# MCU.net
KiCad netlist of a schematic drawn in Altium Designer
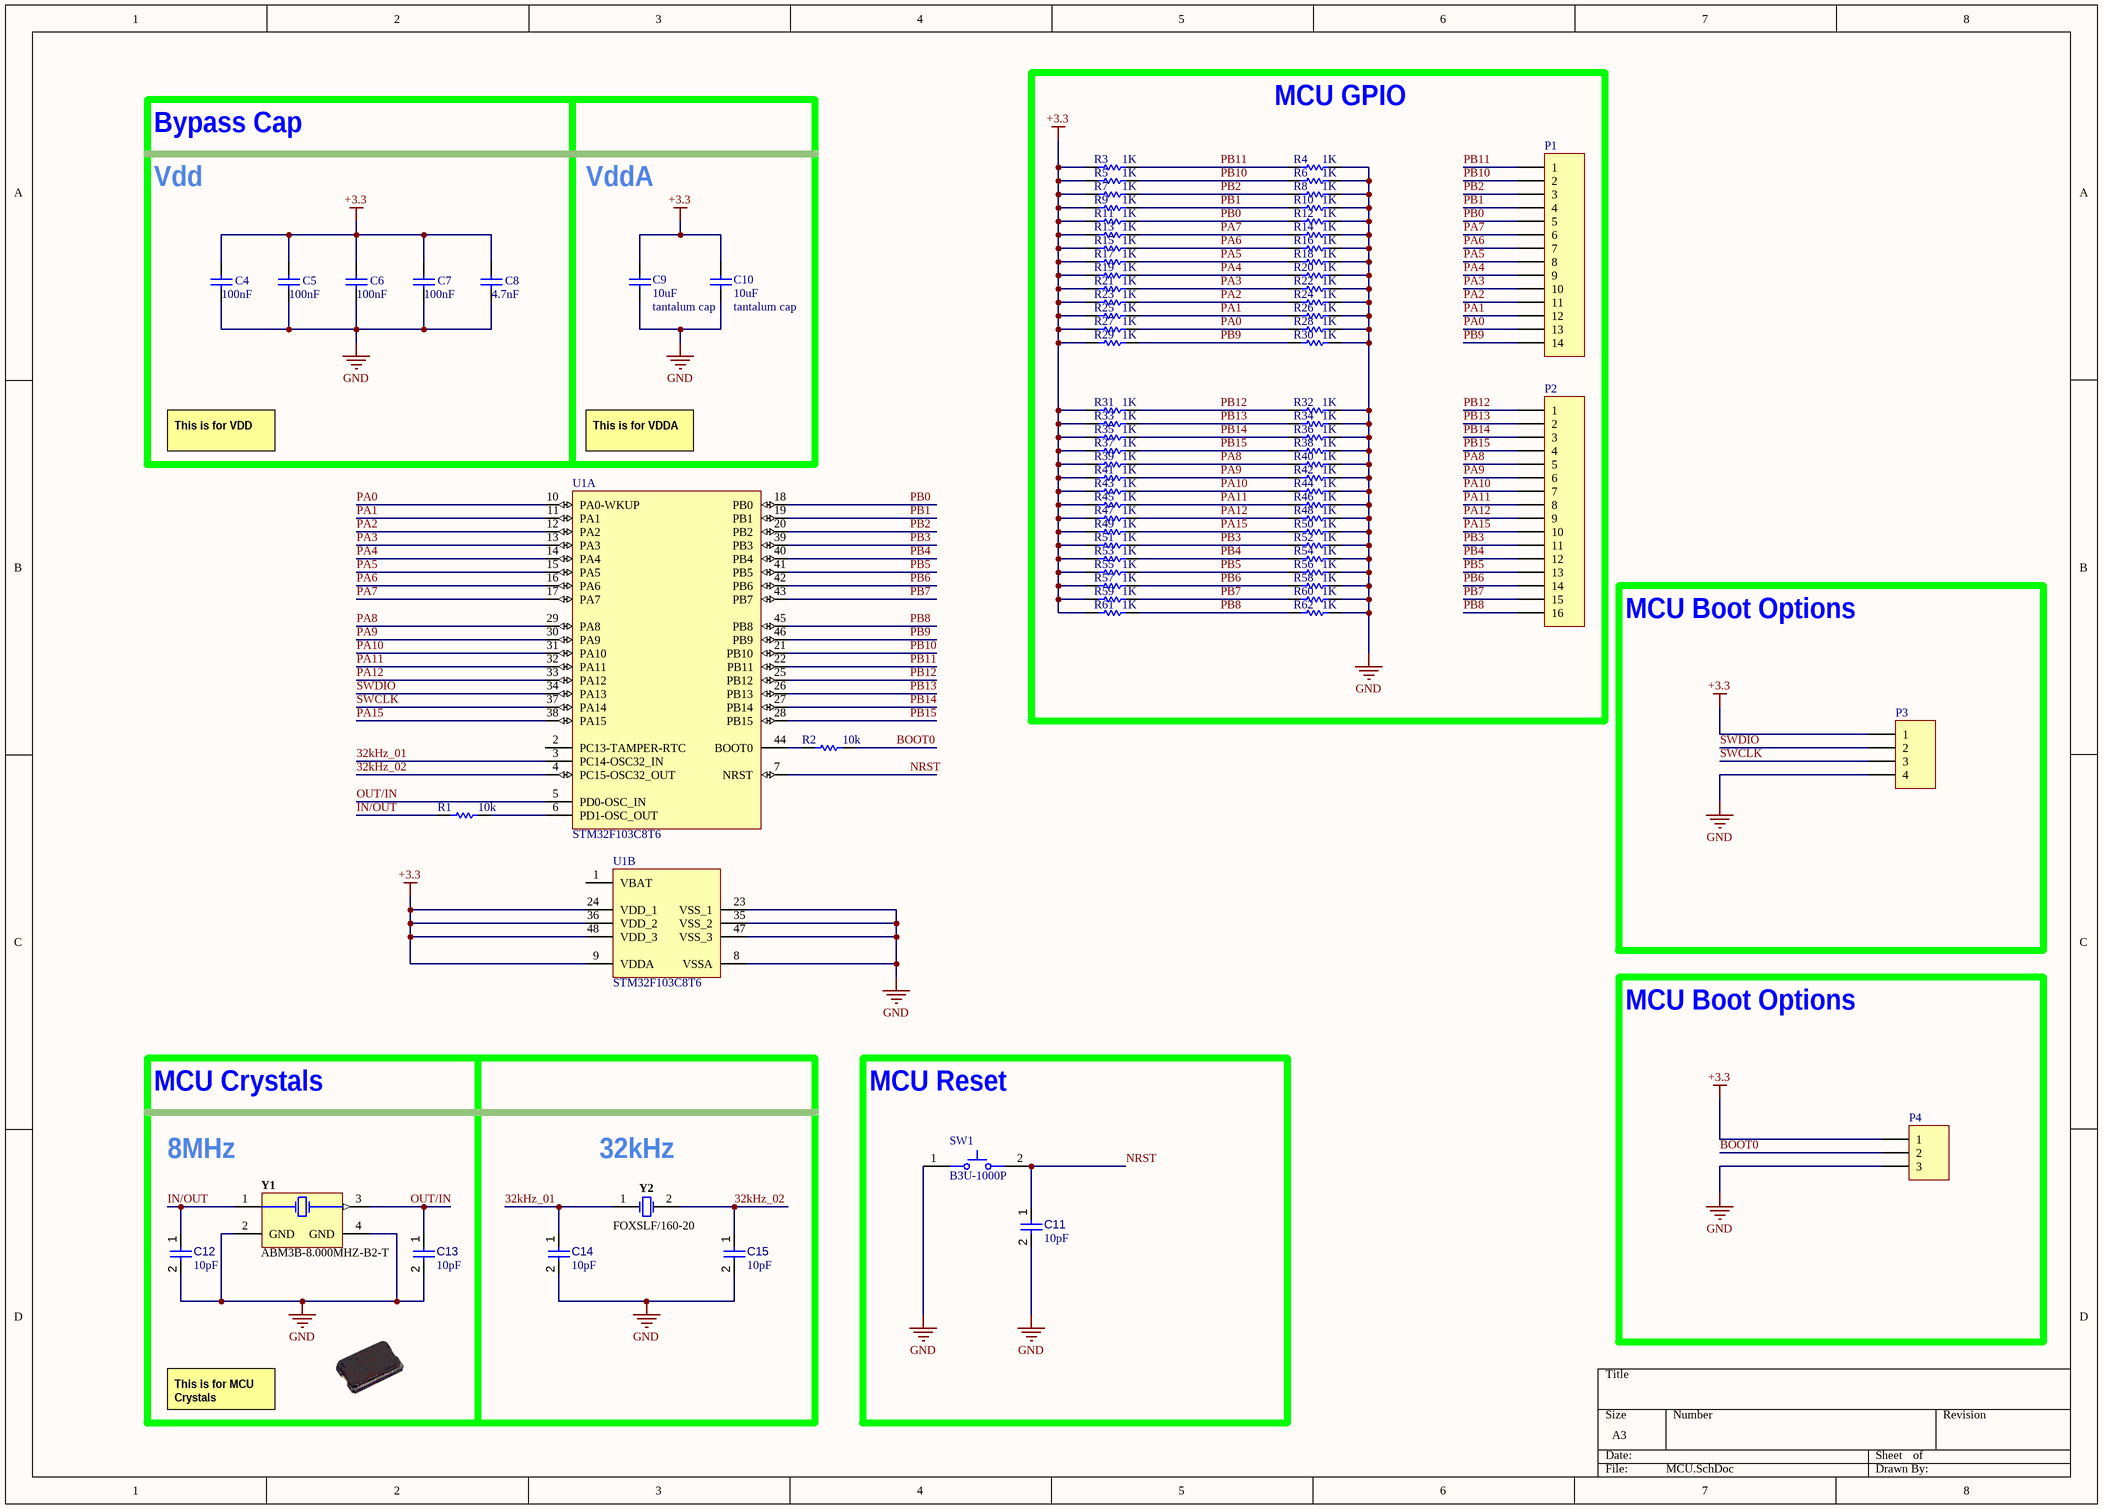
[diagram p0: MCU.SchDoc]

(export (version "E")
  (design (tool "Eeschema 10.0.6"))
  (components
    (comp (ref "C4")
      (value "100nF")
      (footprint "1608[0603]cap")
      (description "Capacitor (Semiconductor SIM Model)")
      (fields (field (name "Comment") "Cap Semi_1") (field (name "PUBLISHER") "Altium Limited"))
      (libsource (lib "smartmcu") (part "Cap Semi_1"))
    )
    (comp (ref "C5")
      (value "100nF")
      (footprint "CAPC2013X135X45NL10T25")
      (description "Capacitor (Semiconductor SIM Model)")
      (fields
        (field (name "Comment") "Capacitor 1 uF +/- 10% 50 V 0805")
        (field (name "PUBLISHER") "Altium Limited")
      )
      (libsource (lib "smartmcu") (part "Cap Semi_1"))
    )
    (comp (ref "C6")
      (value "100nF")
      (footprint "CAPC2013X135X45NL10T25")
      (description "Capacitor (Semiconductor SIM Model)")
      (fields
        (field (name "Comment") "Capacitor 1 uF +/- 10% 50 V 0805")
        (field (name "PUBLISHER") "Altium Limited")
      )
      (libsource (lib "smartmcu") (part "Cap Semi_1"))
    )
    (comp (ref "C7")
      (value "100nF")
      (footprint "CAPC2013X135X45NL10T25")
      (description "Capacitor (Semiconductor SIM Model)")
      (fields
        (field (name "Comment") "Capacitor 1 uF +/- 10% 50 V 0805")
        (field (name "PUBLISHER") "Altium Limited")
      )
      (libsource (lib "smartmcu") (part "Cap Semi_1"))
    )
    (comp (ref "C8")
      (value "4.7nF")
      (footprint "CAPC2013X135X45NL10T25")
      (description "Capacitor (Semiconductor SIM Model)")
      (fields
        (field (name "Comment") "Capacitor 1 uF +/- 10% 50 V 0805")
        (field (name "PUBLISHER") "Altium Limited")
      )
      (libsource (lib "smartmcu") (part "Cap Semi_1"))
    )
    (comp (ref "C9")
      (value "tantalum cap")
      (footprint "C1206tancap")
      (description "Capacitor (Semiconductor SIM Model)")
      (fields (field (name "ALTIUM_VALUE") "10uF") (field (name "PUBLISHER") "Altium Limited"))
      (libsource (lib "smartmcu") (part "Cap Semi_5"))
    )
    (comp (ref "C10")
      (value "tantalum cap")
      (footprint "C1206tancap")
      (description "Capacitor (Semiconductor SIM Model)")
      (fields (field (name "ALTIUM_VALUE") "10uF") (field (name "PUBLISHER") "Altium Limited"))
      (libsource (lib "smartmcu") (part "Cap Semi_5"))
    )
    (comp (ref "C11")
      (value "10pF")
      (footprint "CAPC1005X55X25ML05T05")
      (description "Chip Capacitor, 10 pF, +/- 5%, 50 V, 0402 (1005 Metric)")
      (fields (field (name "TOLERANCE") "5%") (field (name "Comment") "Capacitor 10 pF +/- 5% 50 V 0402"))
      (libsource (lib "Averna Test Systems") (part "CAP-NP-2"))
    )
    (comp (ref "C12")
      (value "10pF")
      (footprint "CAPC1005X55X25ML05T05")
      (description "Chip Capacitor, 10 pF, +/- 5%, 50 V, 0402 (1005 Metric)")
      (fields (field (name "TOLERANCE") "5%") (field (name "Comment") "Capacitor 10 pF +/- 5% 50 V 0402"))
      (libsource (lib "Averna Test Systems") (part "CAP-NP-2"))
    )
    (comp (ref "C13")
      (value "10pF")
      (footprint "CAPC1005X55X25ML05T05")
      (description "Chip Capacitor, 10 pF, +/- 5%, 50 V, 0402 (1005 Metric)")
      (fields (field (name "TOLERANCE") "5%") (field (name "Comment") "Capacitor 10 pF +/- 5% 50 V 0402"))
      (libsource (lib "Averna Test Systems") (part "CAP-NP-2"))
    )
    (comp (ref "C14")
      (value "10pF")
      (footprint "CAPC1005X55X25ML05T05")
      (description "Chip Capacitor, 10 pF, +/- 5%, 50 V, 0402 (1005 Metric)")
      (fields (field (name "TOLERANCE") "5%") (field (name "Comment") "Capacitor 10 pF +/- 5% 50 V 0402"))
      (libsource (lib "Averna Test Systems") (part "CAP-NP-2"))
    )
    (comp (ref "C15")
      (value "10pF")
      (footprint "CAPC1005X55X25ML05T05")
      (description "Chip Capacitor, 10 pF, +/- 5%, 50 V, 0402 (1005 Metric)")
      (fields (field (name "TOLERANCE") "5%") (field (name "Comment") "Capacitor 10 pF +/- 5% 50 V 0402"))
      (libsource (lib "Averna Test Systems") (part "CAP-NP-2"))
    )
    (comp (ref "P1")
      (value "Header 14")
      (footprint "My_1X14")
      (description "Header, 14-Pin")
      (fields (field (name "ASID PART NUMBER") "Header 14-AS"))
      (libsource (lib "Mylib_Rev_4") (part "Header 14"))
    )
    (comp (ref "P2")
      (value "Header 16")
      (footprint "MY_FE16")
      (description "Header, 16-Pin")
      (fields (field (name "ASID PART NUMBER") "Header 16-AS"))
      (libsource (lib "Mylib_Rev_4") (part "Header 16"))
    )
    (comp (ref "P3")
      (value "Header 4")
      (footprint "My_1X04")
      (description "Header, 4-Pin")
      (fields (field (name "ASID PART NUMBER") "Header 4-AS"))
      (libsource (lib "Mylib_Rev_4") (part "Header 4"))
    )
    (comp (ref "P4")
      (value "Header 3")
      (footprint "My_1X03")
      (description "Header, 3-Pin")
      (fields (field (name "ASID PART NUMBER") "Header 3-AS"))
      (libsource (lib "Mylib_Rev_4") (part "Header 3"))
    )
    (comp (ref "R1")
      (value "10k")
      (footprint "MY_0603")
      (description "Standard resistor")
      (fields (field (name "ASID PART NUMBER") "Res-AS"))
      (libsource (lib "Mylib_Rev_4") (part "Res"))
    )
    (comp (ref "R2")
      (value "10k")
      (footprint "MY_0603")
      (description "Standard resistor")
      (fields (field (name "ASID PART NUMBER") "Res-AS"))
      (libsource (lib "Mylib_Rev_4") (part "Res"))
    )
    (comp (ref "R3")
      (value "1K")
      (footprint "MY_0603")
      (description "Standard resistor")
      (fields (field (name "ASID PART NUMBER") "Res-AS"))
      (libsource (lib "Mylib_Rev_4") (part "Res"))
    )
    (comp (ref "R4")
      (value "1K")
      (footprint "MY_0603")
      (description "Standard resistor")
      (fields (field (name "ASID PART NUMBER") "Res-AS"))
      (libsource (lib "Mylib_Rev_4") (part "Res"))
    )
    (comp (ref "R5")
      (value "1K")
      (footprint "MY_0603")
      (description "Standard resistor")
      (fields (field (name "ASID PART NUMBER") "Res-AS"))
      (libsource (lib "Mylib_Rev_4") (part "Res"))
    )
    (comp (ref "R6")
      (value "1K")
      (footprint "MY_0603")
      (description "Standard resistor")
      (fields (field (name "ASID PART NUMBER") "Res-AS"))
      (libsource (lib "Mylib_Rev_4") (part "Res"))
    )
    (comp (ref "R7")
      (value "1K")
      (footprint "MY_0603")
      (description "Standard resistor")
      (fields (field (name "ASID PART NUMBER") "Res-AS"))
      (libsource (lib "Mylib_Rev_4") (part "Res"))
    )
    (comp (ref "R8")
      (value "1K")
      (footprint "MY_0603")
      (description "Standard resistor")
      (fields (field (name "ASID PART NUMBER") "Res-AS"))
      (libsource (lib "Mylib_Rev_4") (part "Res"))
    )
    (comp (ref "R9")
      (value "1K")
      (footprint "MY_0603")
      (description "Standard resistor")
      (fields (field (name "ASID PART NUMBER") "Res-AS"))
      (libsource (lib "Mylib_Rev_4") (part "Res"))
    )
    (comp (ref "R10")
      (value "1K")
      (footprint "MY_0603")
      (description "Standard resistor")
      (fields (field (name "ASID PART NUMBER") "Res-AS"))
      (libsource (lib "Mylib_Rev_4") (part "Res"))
    )
    (comp (ref "R11")
      (value "1K")
      (footprint "MY_0603")
      (description "Standard resistor")
      (fields (field (name "ASID PART NUMBER") "Res-AS"))
      (libsource (lib "Mylib_Rev_4") (part "Res"))
    )
    (comp (ref "R12")
      (value "1K")
      (footprint "MY_0603")
      (description "Standard resistor")
      (fields (field (name "ASID PART NUMBER") "Res-AS"))
      (libsource (lib "Mylib_Rev_4") (part "Res"))
    )
    (comp (ref "R13")
      (value "1K")
      (footprint "MY_0603")
      (description "Standard resistor")
      (fields (field (name "ASID PART NUMBER") "Res-AS"))
      (libsource (lib "Mylib_Rev_4") (part "Res"))
    )
    (comp (ref "R14")
      (value "1K")
      (footprint "MY_0603")
      (description "Standard resistor")
      (fields (field (name "ASID PART NUMBER") "Res-AS"))
      (libsource (lib "Mylib_Rev_4") (part "Res"))
    )
    (comp (ref "R15")
      (value "1K")
      (footprint "MY_0603")
      (description "Standard resistor")
      (fields (field (name "ASID PART NUMBER") "Res-AS"))
      (libsource (lib "Mylib_Rev_4") (part "Res"))
    )
    (comp (ref "R16")
      (value "1K")
      (footprint "MY_0603")
      (description "Standard resistor")
      (fields (field (name "ASID PART NUMBER") "Res-AS"))
      (libsource (lib "Mylib_Rev_4") (part "Res"))
    )
    (comp (ref "R17")
      (value "1K")
      (footprint "MY_0603")
      (description "Standard resistor")
      (fields (field (name "ASID PART NUMBER") "Res-AS"))
      (libsource (lib "Mylib_Rev_4") (part "Res"))
    )
    (comp (ref "R18")
      (value "1K")
      (footprint "MY_0603")
      (description "Standard resistor")
      (fields (field (name "ASID PART NUMBER") "Res-AS"))
      (libsource (lib "Mylib_Rev_4") (part "Res"))
    )
    (comp (ref "R19")
      (value "1K")
      (footprint "MY_0603")
      (description "Standard resistor")
      (fields (field (name "ASID PART NUMBER") "Res-AS"))
      (libsource (lib "Mylib_Rev_4") (part "Res"))
    )
    (comp (ref "R20")
      (value "1K")
      (footprint "MY_0603")
      (description "Standard resistor")
      (fields (field (name "ASID PART NUMBER") "Res-AS"))
      (libsource (lib "Mylib_Rev_4") (part "Res"))
    )
    (comp (ref "R21")
      (value "1K")
      (footprint "MY_0603")
      (description "Standard resistor")
      (fields (field (name "ASID PART NUMBER") "Res-AS"))
      (libsource (lib "Mylib_Rev_4") (part "Res"))
    )
    (comp (ref "R22")
      (value "1K")
      (footprint "MY_0603")
      (description "Standard resistor")
      (fields (field (name "ASID PART NUMBER") "Res-AS"))
      (libsource (lib "Mylib_Rev_4") (part "Res"))
    )
    (comp (ref "R23")
      (value "1K")
      (footprint "MY_0603")
      (description "Standard resistor")
      (fields (field (name "ASID PART NUMBER") "Res-AS"))
      (libsource (lib "Mylib_Rev_4") (part "Res"))
    )
    (comp (ref "R24")
      (value "1K")
      (footprint "MY_0603")
      (description "Standard resistor")
      (fields (field (name "ASID PART NUMBER") "Res-AS"))
      (libsource (lib "Mylib_Rev_4") (part "Res"))
    )
    (comp (ref "R25")
      (value "1K")
      (footprint "MY_0603")
      (description "Standard resistor")
      (fields (field (name "ASID PART NUMBER") "Res-AS"))
      (libsource (lib "Mylib_Rev_4") (part "Res"))
    )
    (comp (ref "R26")
      (value "1K")
      (footprint "MY_0603")
      (description "Standard resistor")
      (fields (field (name "ASID PART NUMBER") "Res-AS"))
      (libsource (lib "Mylib_Rev_4") (part "Res"))
    )
    (comp (ref "R27")
      (value "1K")
      (footprint "MY_0603")
      (description "Standard resistor")
      (fields (field (name "ASID PART NUMBER") "Res-AS"))
      (libsource (lib "Mylib_Rev_4") (part "Res"))
    )
    (comp (ref "R28")
      (value "1K")
      (footprint "MY_0603")
      (description "Standard resistor")
      (fields (field (name "ASID PART NUMBER") "Res-AS"))
      (libsource (lib "Mylib_Rev_4") (part "Res"))
    )
    (comp (ref "R29")
      (value "1K")
      (footprint "MY_0603")
      (description "Standard resistor")
      (fields (field (name "ASID PART NUMBER") "Res-AS"))
      (libsource (lib "Mylib_Rev_4") (part "Res"))
    )
    (comp (ref "R30")
      (value "1K")
      (footprint "MY_0603")
      (description "Standard resistor")
      (fields (field (name "ASID PART NUMBER") "Res-AS"))
      (libsource (lib "Mylib_Rev_4") (part "Res"))
    )
    (comp (ref "R31")
      (value "1K")
      (footprint "MY_0603")
      (description "Standard resistor")
      (fields (field (name "ASID PART NUMBER") "Res-AS"))
      (libsource (lib "Mylib_Rev_4") (part "Res"))
    )
    (comp (ref "R32")
      (value "1K")
      (footprint "MY_0603")
      (description "Standard resistor")
      (fields (field (name "ASID PART NUMBER") "Res-AS"))
      (libsource (lib "Mylib_Rev_4") (part "Res"))
    )
    (comp (ref "R33")
      (value "1K")
      (footprint "MY_0603")
      (description "Standard resistor")
      (fields (field (name "ASID PART NUMBER") "Res-AS"))
      (libsource (lib "Mylib_Rev_4") (part "Res"))
    )
    (comp (ref "R34")
      (value "1K")
      (footprint "MY_0603")
      (description "Standard resistor")
      (fields (field (name "ASID PART NUMBER") "Res-AS"))
      (libsource (lib "Mylib_Rev_4") (part "Res"))
    )
    (comp (ref "R35")
      (value "1K")
      (footprint "MY_0603")
      (description "Standard resistor")
      (fields (field (name "ASID PART NUMBER") "Res-AS"))
      (libsource (lib "Mylib_Rev_4") (part "Res"))
    )
    (comp (ref "R36")
      (value "1K")
      (footprint "MY_0603")
      (description "Standard resistor")
      (fields (field (name "ASID PART NUMBER") "Res-AS"))
      (libsource (lib "Mylib_Rev_4") (part "Res"))
    )
    (comp (ref "R37")
      (value "1K")
      (footprint "MY_0603")
      (description "Standard resistor")
      (fields (field (name "ASID PART NUMBER") "Res-AS"))
      (libsource (lib "Mylib_Rev_4") (part "Res"))
    )
    (comp (ref "R38")
      (value "1K")
      (footprint "MY_0603")
      (description "Standard resistor")
      (fields (field (name "ASID PART NUMBER") "Res-AS"))
      (libsource (lib "Mylib_Rev_4") (part "Res"))
    )
    (comp (ref "R39")
      (value "1K")
      (footprint "MY_0603")
      (description "Standard resistor")
      (fields (field (name "ASID PART NUMBER") "Res-AS"))
      (libsource (lib "Mylib_Rev_4") (part "Res"))
    )
    (comp (ref "R40")
      (value "1K")
      (footprint "MY_0603")
      (description "Standard resistor")
      (fields (field (name "ASID PART NUMBER") "Res-AS"))
      (libsource (lib "Mylib_Rev_4") (part "Res"))
    )
    (comp (ref "R41")
      (value "1K")
      (footprint "MY_0603")
      (description "Standard resistor")
      (fields (field (name "ASID PART NUMBER") "Res-AS"))
      (libsource (lib "Mylib_Rev_4") (part "Res"))
    )
    (comp (ref "R42")
      (value "1K")
      (footprint "MY_0603")
      (description "Standard resistor")
      (fields (field (name "ASID PART NUMBER") "Res-AS"))
      (libsource (lib "Mylib_Rev_4") (part "Res"))
    )
    (comp (ref "R43")
      (value "1K")
      (footprint "MY_0603")
      (description "Standard resistor")
      (fields (field (name "ASID PART NUMBER") "Res-AS"))
      (libsource (lib "Mylib_Rev_4") (part "Res"))
    )
    (comp (ref "R44")
      (value "1K")
      (footprint "MY_0603")
      (description "Standard resistor")
      (fields (field (name "ASID PART NUMBER") "Res-AS"))
      (libsource (lib "Mylib_Rev_4") (part "Res"))
    )
    (comp (ref "R45")
      (value "1K")
      (footprint "MY_0603")
      (description "Standard resistor")
      (fields (field (name "ASID PART NUMBER") "Res-AS"))
      (libsource (lib "Mylib_Rev_4") (part "Res"))
    )
    (comp (ref "R46")
      (value "1K")
      (footprint "MY_0603")
      (description "Standard resistor")
      (fields (field (name "ASID PART NUMBER") "Res-AS"))
      (libsource (lib "Mylib_Rev_4") (part "Res"))
    )
    (comp (ref "R47")
      (value "1K")
      (footprint "MY_0603")
      (description "Standard resistor")
      (fields (field (name "ASID PART NUMBER") "Res-AS"))
      (libsource (lib "Mylib_Rev_4") (part "Res"))
    )
    (comp (ref "R48")
      (value "1K")
      (footprint "MY_0603")
      (description "Standard resistor")
      (fields (field (name "ASID PART NUMBER") "Res-AS"))
      (libsource (lib "Mylib_Rev_4") (part "Res"))
    )
    (comp (ref "R49")
      (value "1K")
      (footprint "MY_0603")
      (description "Standard resistor")
      (fields (field (name "ASID PART NUMBER") "Res-AS"))
      (libsource (lib "Mylib_Rev_4") (part "Res"))
    )
    (comp (ref "R50")
      (value "1K")
      (footprint "MY_0603")
      (description "Standard resistor")
      (fields (field (name "ASID PART NUMBER") "Res-AS"))
      (libsource (lib "Mylib_Rev_4") (part "Res"))
    )
    (comp (ref "R51")
      (value "1K")
      (footprint "MY_0603")
      (description "Standard resistor")
      (fields (field (name "ASID PART NUMBER") "Res-AS"))
      (libsource (lib "Mylib_Rev_4") (part "Res"))
    )
    (comp (ref "R52")
      (value "1K")
      (footprint "MY_0603")
      (description "Standard resistor")
      (fields (field (name "ASID PART NUMBER") "Res-AS"))
      (libsource (lib "Mylib_Rev_4") (part "Res"))
    )
    (comp (ref "R53")
      (value "1K")
      (footprint "MY_0603")
      (description "Standard resistor")
      (fields (field (name "ASID PART NUMBER") "Res-AS"))
      (libsource (lib "Mylib_Rev_4") (part "Res"))
    )
    (comp (ref "R54")
      (value "1K")
      (footprint "MY_0603")
      (description "Standard resistor")
      (fields (field (name "ASID PART NUMBER") "Res-AS"))
      (libsource (lib "Mylib_Rev_4") (part "Res"))
    )
    (comp (ref "R55")
      (value "1K")
      (footprint "MY_0603")
      (description "Standard resistor")
      (fields (field (name "ASID PART NUMBER") "Res-AS"))
      (libsource (lib "Mylib_Rev_4") (part "Res"))
    )
    (comp (ref "R56")
      (value "1K")
      (footprint "MY_0603")
      (description "Standard resistor")
      (fields (field (name "ASID PART NUMBER") "Res-AS"))
      (libsource (lib "Mylib_Rev_4") (part "Res"))
    )
    (comp (ref "R57")
      (value "1K")
      (footprint "MY_0603")
      (description "Standard resistor")
      (fields (field (name "ASID PART NUMBER") "Res-AS"))
      (libsource (lib "Mylib_Rev_4") (part "Res"))
    )
    (comp (ref "R58")
      (value "1K")
      (footprint "MY_0603")
      (description "Standard resistor")
      (fields (field (name "ASID PART NUMBER") "Res-AS"))
      (libsource (lib "Mylib_Rev_4") (part "Res"))
    )
    (comp (ref "R59")
      (value "1K")
      (footprint "MY_0603")
      (description "Standard resistor")
      (fields (field (name "ASID PART NUMBER") "Res-AS"))
      (libsource (lib "Mylib_Rev_4") (part "Res"))
    )
    (comp (ref "R60")
      (value "1K")
      (footprint "MY_0603")
      (description "Standard resistor")
      (fields (field (name "ASID PART NUMBER") "Res-AS"))
      (libsource (lib "Mylib_Rev_4") (part "Res"))
    )
    (comp (ref "R61")
      (value "1K")
      (footprint "MY_0603")
      (description "Standard resistor")
      (fields (field (name "ASID PART NUMBER") "Res-AS"))
      (libsource (lib "Mylib_Rev_4") (part "Res"))
    )
    (comp (ref "R62")
      (value "1K")
      (footprint "MY_0603")
      (description "Standard resistor")
      (fields (field (name "ASID PART NUMBER") "Res-AS"))
      (libsource (lib "Mylib_Rev_4") (part "Res"))
    )
    (comp (ref "SW1")
      (value "B3U-1000P")
      (footprint "OMRON-B3U-1000_V")
      (description "Tactile Switch, SPST-NO, 0.05 A, 12 V, -25 to 70 degC, 2-Pin SMD, RoHS, Tape and Reel")
      (fields (field (name "MANUFACTURER") "Omron Electronic Components"))
      (libsource (lib "Averna Test Systems") (part "SW-SPST-NO-2"))
    )
    (comp (ref "U1")
      (value "STM32F103C8T6")
      (footprint "STM-LQFP48_L")
      (libsource (lib "Altium Content Vault") (part "MC-ARM-STM32F103X8_B-SQ48"))
    )
    (comp (ref "Y1")
      (value "ABM3B-8.000MHZ-B2-T")
      (footprint "ABRA-ABM3B_V")
      (description "Ceramic SMD Crystal, 8 MHz, +/- 20 ppm, 18 pF, -20 to 70 degC, 4-Pin SMD, RoHS, Tape and Reel")
      (fields (field (name "TOLERANCE") "20ppm") (field (name "MANUFACTURER") "Abracon"))
      (libsource (lib "Averna Test Systems") (part "XTAL-1-3-4"))
    )
    (comp (ref "Y2")
      (value "FOXSLF/160-20")
      (footprint "FOX-FOXSLF160-20")
      (fields (field (name "MANUFACTURER") "FOX Electronics") (field (name "TOLERANCE") "50ppm"))
      (libsource (lib "Averna Test Systems") (part "XTAL-1-2-2"))
    )
  )
  (nets
    (net (code "1") (name "+3.3") (class "Default")
      (node (ref "C10") (pin "2") (pinfunction "2_2") (pintype "passive"))
      (node (ref "C4") (pin "2") (pinfunction "2_2") (pintype "passive"))
      (node (ref "C5") (pin "2") (pinfunction "2_2") (pintype "passive"))
      (node (ref "C6") (pin "2") (pinfunction "2_2") (pintype "passive"))
      (node (ref "C7") (pin "2") (pinfunction "2_2") (pintype "passive"))
      (node (ref "C8") (pin "2") (pinfunction "2_2") (pintype "passive"))
      (node (ref "C9") (pin "2") (pinfunction "2_2") (pintype "passive"))
      (node (ref "P3") (pin "1") (pinfunction "1_1") (pintype "passive"))
      (node (ref "P4") (pin "1") (pinfunction "1_1") (pintype "passive"))
      (node (ref "R11") (pin "1") (pinfunction "1_1") (pintype "passive"))
      (node (ref "R13") (pin "1") (pinfunction "1_1") (pintype "passive"))
      (node (ref "R15") (pin "1") (pinfunction "1_1") (pintype "passive"))
      (node (ref "R17") (pin "1") (pinfunction "1_1") (pintype "passive"))
      (node (ref "R19") (pin "1") (pinfunction "1_1") (pintype "passive"))
      (node (ref "R21") (pin "1") (pinfunction "1_1") (pintype "passive"))
      (node (ref "R23") (pin "1") (pinfunction "1_1") (pintype "passive"))
      (node (ref "R25") (pin "1") (pinfunction "1_1") (pintype "passive"))
      (node (ref "R27") (pin "1") (pinfunction "1_1") (pintype "passive"))
      (node (ref "R29") (pin "1") (pinfunction "1_1") (pintype "passive"))
      (node (ref "R3") (pin "1") (pinfunction "1_1") (pintype "passive"))
      (node (ref "R31") (pin "1") (pinfunction "1_1") (pintype "passive"))
      (node (ref "R33") (pin "1") (pinfunction "1_1") (pintype "passive"))
      (node (ref "R35") (pin "1") (pinfunction "1_1") (pintype "passive"))
      (node (ref "R37") (pin "1") (pinfunction "1_1") (pintype "passive"))
      (node (ref "R39") (pin "1") (pinfunction "1_1") (pintype "passive"))
      (node (ref "R41") (pin "1") (pinfunction "1_1") (pintype "passive"))
      (node (ref "R43") (pin "1") (pinfunction "1_1") (pintype "passive"))
      (node (ref "R45") (pin "1") (pinfunction "1_1") (pintype "passive"))
      (node (ref "R47") (pin "1") (pinfunction "1_1") (pintype "passive"))
      (node (ref "R49") (pin "1") (pinfunction "1_1") (pintype "passive"))
      (node (ref "R5") (pin "1") (pinfunction "1_1") (pintype "passive"))
      (node (ref "R51") (pin "1") (pinfunction "1_1") (pintype "passive"))
      (node (ref "R53") (pin "1") (pinfunction "1_1") (pintype "passive"))
      (node (ref "R55") (pin "1") (pinfunction "1_1") (pintype "passive"))
      (node (ref "R57") (pin "1") (pinfunction "1_1") (pintype "passive"))
      (node (ref "R59") (pin "1") (pinfunction "1_1") (pintype "passive"))
      (node (ref "R61") (pin "1") (pinfunction "1_1") (pintype "passive"))
      (node (ref "R7") (pin "1") (pinfunction "1_1") (pintype "passive"))
      (node (ref "R9") (pin "1") (pinfunction "1_1") (pintype "passive"))
      (node (ref "U1") (pin "24") (pinfunction "VDD_1_24") (pintype "power_in"))
      (node (ref "U1") (pin "36") (pinfunction "VDD_2_36") (pintype "power_in"))
      (node (ref "U1") (pin "48") (pinfunction "VDD_3_48") (pintype "power_in"))
      (node (ref "U1") (pin "9") (pinfunction "VDDA_9") (pintype "power_in"))
    )
    (net (code "2") (name "/32kHz_01") (class "Default")
      (node (ref "C14") (pin "1") (pinfunction "1_1") (pintype "passive"))
      (node (ref "U1") (pin "3") (pinfunction "PC14-OSC32_IN_3") (pintype "passive"))
      (node (ref "Y2") (pin "1") (pinfunction "1_1") (pintype "passive"))
    )
    (net (code "3") (name "/32kHz_02") (class "Default")
      (node (ref "C15") (pin "1") (pinfunction "1_1") (pintype "passive"))
      (node (ref "U1") (pin "4") (pinfunction "PC15-OSC32_OUT_4") (pintype "bidirectional"))
      (node (ref "Y2") (pin "2") (pinfunction "2_2") (pintype "passive"))
    )
    (net (code "4") (name "/BOOT0") (class "Default")
      (node (ref "P4") (pin "2") (pinfunction "2_2") (pintype "passive"))
      (node (ref "R2") (pin "2") (pinfunction "2_2") (pintype "passive"))
    )
    (net (code "5") (name "/IN{slash}OUT") (class "Default")
      (node (ref "C12") (pin "1") (pinfunction "1_1") (pintype "passive"))
      (node (ref "R1") (pin "1") (pinfunction "1_1") (pintype "passive"))
      (node (ref "Y1") (pin "1") (pinfunction "X1_1") (pintype "passive"))
    )
    (net (code "6") (name "/NRST") (class "Default")
      (node (ref "C11") (pin "1") (pinfunction "1_1") (pintype "passive"))
      (node (ref "SW1") (pin "2") (pinfunction "2_2") (pintype "passive"))
      (node (ref "U1") (pin "7") (pinfunction "NRST_7") (pintype "bidirectional"))
    )
    (net (code "7") (name "/OUT{slash}IN") (class "Default")
      (node (ref "C13") (pin "1") (pinfunction "1_1") (pintype "passive"))
      (node (ref "U1") (pin "5") (pinfunction "PD0-OSC_IN_5") (pintype "passive"))
      (node (ref "Y1") (pin "3") (pinfunction "X2_3") (pintype "output"))
    )
    (net (code "8") (name "/PA0") (class "Default")
      (node (ref "P1") (pin "13") (pinfunction "13_13") (pintype "passive"))
      (node (ref "R27") (pin "2") (pinfunction "2_2") (pintype "passive"))
      (node (ref "R28") (pin "1") (pinfunction "1_1") (pintype "passive"))
      (node (ref "U1") (pin "10") (pinfunction "PA0-WKUP_10") (pintype "bidirectional"))
    )
    (net (code "9") (name "/PA1") (class "Default")
      (node (ref "P1") (pin "12") (pinfunction "12_12") (pintype "passive"))
      (node (ref "R25") (pin "2") (pinfunction "2_2") (pintype "passive"))
      (node (ref "R26") (pin "1") (pinfunction "1_1") (pintype "passive"))
      (node (ref "U1") (pin "11") (pinfunction "PA1_11") (pintype "bidirectional"))
    )
    (net (code "10") (name "/PA2") (class "Default")
      (node (ref "P1") (pin "11") (pinfunction "11_11") (pintype "passive"))
      (node (ref "R23") (pin "2") (pinfunction "2_2") (pintype "passive"))
      (node (ref "R24") (pin "1") (pinfunction "1_1") (pintype "passive"))
      (node (ref "U1") (pin "12") (pinfunction "PA2_12") (pintype "bidirectional"))
    )
    (net (code "11") (name "/PA3") (class "Default")
      (node (ref "P1") (pin "10") (pinfunction "10_10") (pintype "passive"))
      (node (ref "R21") (pin "2") (pinfunction "2_2") (pintype "passive"))
      (node (ref "R22") (pin "1") (pinfunction "1_1") (pintype "passive"))
      (node (ref "U1") (pin "13") (pinfunction "PA3_13") (pintype "bidirectional"))
    )
    (net (code "12") (name "/PA4") (class "Default")
      (node (ref "P1") (pin "9") (pinfunction "9_9") (pintype "passive"))
      (node (ref "R19") (pin "2") (pinfunction "2_2") (pintype "passive"))
      (node (ref "R20") (pin "1") (pinfunction "1_1") (pintype "passive"))
      (node (ref "U1") (pin "14") (pinfunction "PA4_14") (pintype "bidirectional"))
    )
    (net (code "13") (name "/PA5") (class "Default")
      (node (ref "P1") (pin "8") (pinfunction "8_8") (pintype "passive"))
      (node (ref "R17") (pin "2") (pinfunction "2_2") (pintype "passive"))
      (node (ref "R18") (pin "1") (pinfunction "1_1") (pintype "passive"))
      (node (ref "U1") (pin "15") (pinfunction "PA5_15") (pintype "bidirectional"))
    )
    (net (code "14") (name "/PA6") (class "Default")
      (node (ref "P1") (pin "7") (pinfunction "7_7") (pintype "passive"))
      (node (ref "R15") (pin "2") (pinfunction "2_2") (pintype "passive"))
      (node (ref "R16") (pin "1") (pinfunction "1_1") (pintype "passive"))
      (node (ref "U1") (pin "16") (pinfunction "PA6_16") (pintype "bidirectional"))
    )
    (net (code "15") (name "/PA7") (class "Default")
      (node (ref "P1") (pin "6") (pinfunction "6_6") (pintype "passive"))
      (node (ref "R13") (pin "2") (pinfunction "2_2") (pintype "passive"))
      (node (ref "R14") (pin "1") (pinfunction "1_1") (pintype "passive"))
      (node (ref "U1") (pin "17") (pinfunction "PA7_17") (pintype "bidirectional"))
    )
    (net (code "16") (name "/PA8") (class "Default")
      (node (ref "P2") (pin "5") (pinfunction "5_5") (pintype "passive"))
      (node (ref "R39") (pin "2") (pinfunction "2_2") (pintype "passive"))
      (node (ref "R40") (pin "1") (pinfunction "1_1") (pintype "passive"))
      (node (ref "U1") (pin "29") (pinfunction "PA8_29") (pintype "bidirectional"))
    )
    (net (code "17") (name "/PA9") (class "Default")
      (node (ref "P2") (pin "6") (pinfunction "6_6") (pintype "passive"))
      (node (ref "R41") (pin "2") (pinfunction "2_2") (pintype "passive"))
      (node (ref "R42") (pin "1") (pinfunction "1_1") (pintype "passive"))
      (node (ref "U1") (pin "30") (pinfunction "PA9_30") (pintype "bidirectional"))
    )
    (net (code "18") (name "/PA10") (class "Default")
      (node (ref "P2") (pin "7") (pinfunction "7_7") (pintype "passive"))
      (node (ref "R43") (pin "2") (pinfunction "2_2") (pintype "passive"))
      (node (ref "R44") (pin "1") (pinfunction "1_1") (pintype "passive"))
      (node (ref "U1") (pin "31") (pinfunction "PA10_31") (pintype "bidirectional"))
    )
    (net (code "19") (name "/PA11") (class "Default")
      (node (ref "P2") (pin "8") (pinfunction "8_8") (pintype "passive"))
      (node (ref "R45") (pin "2") (pinfunction "2_2") (pintype "passive"))
      (node (ref "R46") (pin "1") (pinfunction "1_1") (pintype "passive"))
      (node (ref "U1") (pin "32") (pinfunction "PA11_32") (pintype "bidirectional"))
    )
    (net (code "20") (name "/PA12") (class "Default")
      (node (ref "P2") (pin "9") (pinfunction "9_9") (pintype "passive"))
      (node (ref "R47") (pin "2") (pinfunction "2_2") (pintype "passive"))
      (node (ref "R48") (pin "1") (pinfunction "1_1") (pintype "passive"))
      (node (ref "U1") (pin "33") (pinfunction "PA12_33") (pintype "bidirectional"))
    )
    (net (code "21") (name "/PA15") (class "Default")
      (node (ref "P2") (pin "10") (pinfunction "10_10") (pintype "passive"))
      (node (ref "R49") (pin "2") (pinfunction "2_2") (pintype "passive"))
      (node (ref "R50") (pin "1") (pinfunction "1_1") (pintype "passive"))
      (node (ref "U1") (pin "38") (pinfunction "PA15_38") (pintype "bidirectional"))
    )
    (net (code "22") (name "/PB0") (class "Default")
      (node (ref "P1") (pin "5") (pinfunction "5_5") (pintype "passive"))
      (node (ref "R11") (pin "2") (pinfunction "2_2") (pintype "passive"))
      (node (ref "R12") (pin "1") (pinfunction "1_1") (pintype "passive"))
      (node (ref "U1") (pin "18") (pinfunction "PB0_18") (pintype "bidirectional"))
    )
    (net (code "23") (name "/PB1") (class "Default")
      (node (ref "P1") (pin "4") (pinfunction "4_4") (pintype "passive"))
      (node (ref "R10") (pin "1") (pinfunction "1_1") (pintype "passive"))
      (node (ref "R9") (pin "2") (pinfunction "2_2") (pintype "passive"))
      (node (ref "U1") (pin "19") (pinfunction "PB1_19") (pintype "bidirectional"))
    )
    (net (code "24") (name "/PB2") (class "Default")
      (node (ref "P1") (pin "3") (pinfunction "3_3") (pintype "passive"))
      (node (ref "R7") (pin "2") (pinfunction "2_2") (pintype "passive"))
      (node (ref "R8") (pin "1") (pinfunction "1_1") (pintype "passive"))
      (node (ref "U1") (pin "20") (pinfunction "PB2_20") (pintype "bidirectional"))
    )
    (net (code "25") (name "/PB3") (class "Default")
      (node (ref "P2") (pin "11") (pinfunction "11_11") (pintype "passive"))
      (node (ref "R51") (pin "2") (pinfunction "2_2") (pintype "passive"))
      (node (ref "R52") (pin "1") (pinfunction "1_1") (pintype "passive"))
      (node (ref "U1") (pin "39") (pinfunction "PB3_39") (pintype "bidirectional"))
    )
    (net (code "26") (name "/PB4") (class "Default")
      (node (ref "P2") (pin "12") (pinfunction "12_12") (pintype "passive"))
      (node (ref "R53") (pin "2") (pinfunction "2_2") (pintype "passive"))
      (node (ref "R54") (pin "1") (pinfunction "1_1") (pintype "passive"))
      (node (ref "U1") (pin "40") (pinfunction "PB4_40") (pintype "bidirectional"))
    )
    (net (code "27") (name "/PB5") (class "Default")
      (node (ref "P2") (pin "13") (pinfunction "13_13") (pintype "passive"))
      (node (ref "R55") (pin "2") (pinfunction "2_2") (pintype "passive"))
      (node (ref "R56") (pin "1") (pinfunction "1_1") (pintype "passive"))
      (node (ref "U1") (pin "41") (pinfunction "PB5_41") (pintype "bidirectional"))
    )
    (net (code "28") (name "/PB6") (class "Default")
      (node (ref "P2") (pin "14") (pinfunction "14_14") (pintype "passive"))
      (node (ref "R57") (pin "2") (pinfunction "2_2") (pintype "passive"))
      (node (ref "R58") (pin "1") (pinfunction "1_1") (pintype "passive"))
      (node (ref "U1") (pin "42") (pinfunction "PB6_42") (pintype "bidirectional"))
    )
    (net (code "29") (name "/PB7") (class "Default")
      (node (ref "P2") (pin "15") (pinfunction "15_15") (pintype "passive"))
      (node (ref "R59") (pin "2") (pinfunction "2_2") (pintype "passive"))
      (node (ref "R60") (pin "1") (pinfunction "1_1") (pintype "passive"))
      (node (ref "U1") (pin "43") (pinfunction "PB7_43") (pintype "bidirectional"))
    )
    (net (code "30") (name "/PB8") (class "Default")
      (node (ref "P2") (pin "16") (pinfunction "16_16") (pintype "passive"))
      (node (ref "R61") (pin "2") (pinfunction "2_2") (pintype "passive"))
      (node (ref "R62") (pin "1") (pinfunction "1_1") (pintype "passive"))
      (node (ref "U1") (pin "45") (pinfunction "PB8_45") (pintype "bidirectional"))
    )
    (net (code "31") (name "/PB9") (class "Default")
      (node (ref "P1") (pin "14") (pinfunction "14_14") (pintype "passive"))
      (node (ref "R29") (pin "2") (pinfunction "2_2") (pintype "passive"))
      (node (ref "R30") (pin "1") (pinfunction "1_1") (pintype "passive"))
      (node (ref "U1") (pin "46") (pinfunction "PB9_46") (pintype "bidirectional"))
    )
    (net (code "32") (name "/PB10") (class "Default")
      (node (ref "P1") (pin "2") (pinfunction "2_2") (pintype "passive"))
      (node (ref "R5") (pin "2") (pinfunction "2_2") (pintype "passive"))
      (node (ref "R6") (pin "1") (pinfunction "1_1") (pintype "passive"))
      (node (ref "U1") (pin "21") (pinfunction "PB10_21") (pintype "bidirectional"))
    )
    (net (code "33") (name "/PB11") (class "Default")
      (node (ref "P1") (pin "1") (pinfunction "1_1") (pintype "passive"))
      (node (ref "R3") (pin "2") (pinfunction "2_2") (pintype "passive"))
      (node (ref "R4") (pin "1") (pinfunction "1_1") (pintype "passive"))
      (node (ref "U1") (pin "22") (pinfunction "PB11_22") (pintype "bidirectional"))
    )
    (net (code "34") (name "/PB12") (class "Default")
      (node (ref "P2") (pin "1") (pinfunction "1_1") (pintype "passive"))
      (node (ref "R31") (pin "2") (pinfunction "2_2") (pintype "passive"))
      (node (ref "R32") (pin "1") (pinfunction "1_1") (pintype "passive"))
      (node (ref "U1") (pin "25") (pinfunction "PB12_25") (pintype "bidirectional"))
    )
    (net (code "35") (name "/PB13") (class "Default")
      (node (ref "P2") (pin "2") (pinfunction "2_2") (pintype "passive"))
      (node (ref "R33") (pin "2") (pinfunction "2_2") (pintype "passive"))
      (node (ref "R34") (pin "1") (pinfunction "1_1") (pintype "passive"))
      (node (ref "U1") (pin "26") (pinfunction "PB13_26") (pintype "bidirectional"))
    )
    (net (code "36") (name "/PB14") (class "Default")
      (node (ref "P2") (pin "3") (pinfunction "3_3") (pintype "passive"))
      (node (ref "R35") (pin "2") (pinfunction "2_2") (pintype "passive"))
      (node (ref "R36") (pin "1") (pinfunction "1_1") (pintype "passive"))
      (node (ref "U1") (pin "27") (pinfunction "PB14_27") (pintype "bidirectional"))
    )
    (net (code "37") (name "/PB15") (class "Default")
      (node (ref "P2") (pin "4") (pinfunction "4_4") (pintype "passive"))
      (node (ref "R37") (pin "2") (pinfunction "2_2") (pintype "passive"))
      (node (ref "R38") (pin "1") (pinfunction "1_1") (pintype "passive"))
      (node (ref "U1") (pin "28") (pinfunction "PB15_28") (pintype "bidirectional"))
    )
    (net (code "38") (name "/SWCLK") (class "Default")
      (node (ref "P3") (pin "3") (pinfunction "3_3") (pintype "passive"))
      (node (ref "U1") (pin "37") (pinfunction "PA14_37") (pintype "bidirectional"))
    )
    (net (code "39") (name "/SWDIO") (class "Default")
      (node (ref "P3") (pin "2") (pinfunction "2_2") (pintype "passive"))
      (node (ref "U1") (pin "34") (pinfunction "PA13_34") (pintype "bidirectional"))
    )
    (net (code "40") (name "GND") (class "Default")
      (node (ref "C10") (pin "1") (pinfunction "1_1") (pintype "passive"))
      (node (ref "C11") (pin "2") (pinfunction "2_2") (pintype "passive"))
      (node (ref "C12") (pin "2") (pinfunction "2_2") (pintype "passive"))
      (node (ref "C13") (pin "2") (pinfunction "2_2") (pintype "passive"))
      (node (ref "C14") (pin "2") (pinfunction "2_2") (pintype "passive"))
      (node (ref "C15") (pin "2") (pinfunction "2_2") (pintype "passive"))
      (node (ref "C4") (pin "1") (pinfunction "1_1") (pintype "passive"))
      (node (ref "C5") (pin "1") (pinfunction "1_1") (pintype "passive"))
      (node (ref "C6") (pin "1") (pinfunction "1_1") (pintype "passive"))
      (node (ref "C7") (pin "1") (pinfunction "1_1") (pintype "passive"))
      (node (ref "C8") (pin "1") (pinfunction "1_1") (pintype "passive"))
      (node (ref "C9") (pin "1") (pinfunction "1_1") (pintype "passive"))
      (node (ref "P3") (pin "4") (pinfunction "4_4") (pintype "passive"))
      (node (ref "P4") (pin "3") (pinfunction "3_3") (pintype "passive"))
      (node (ref "R10") (pin "2") (pinfunction "2_2") (pintype "passive"))
      (node (ref "R12") (pin "2") (pinfunction "2_2") (pintype "passive"))
      (node (ref "R14") (pin "2") (pinfunction "2_2") (pintype "passive"))
      (node (ref "R16") (pin "2") (pinfunction "2_2") (pintype "passive"))
      (node (ref "R18") (pin "2") (pinfunction "2_2") (pintype "passive"))
      (node (ref "R20") (pin "2") (pinfunction "2_2") (pintype "passive"))
      (node (ref "R22") (pin "2") (pinfunction "2_2") (pintype "passive"))
      (node (ref "R24") (pin "2") (pinfunction "2_2") (pintype "passive"))
      (node (ref "R26") (pin "2") (pinfunction "2_2") (pintype "passive"))
      (node (ref "R28") (pin "2") (pinfunction "2_2") (pintype "passive"))
      (node (ref "R30") (pin "2") (pinfunction "2_2") (pintype "passive"))
      (node (ref "R32") (pin "2") (pinfunction "2_2") (pintype "passive"))
      (node (ref "R34") (pin "2") (pinfunction "2_2") (pintype "passive"))
      (node (ref "R36") (pin "2") (pinfunction "2_2") (pintype "passive"))
      (node (ref "R38") (pin "2") (pinfunction "2_2") (pintype "passive"))
      (node (ref "R4") (pin "2") (pinfunction "2_2") (pintype "passive"))
      (node (ref "R40") (pin "2") (pinfunction "2_2") (pintype "passive"))
      (node (ref "R42") (pin "2") (pinfunction "2_2") (pintype "passive"))
      (node (ref "R44") (pin "2") (pinfunction "2_2") (pintype "passive"))
      (node (ref "R46") (pin "2") (pinfunction "2_2") (pintype "passive"))
      (node (ref "R48") (pin "2") (pinfunction "2_2") (pintype "passive"))
      (node (ref "R50") (pin "2") (pinfunction "2_2") (pintype "passive"))
      (node (ref "R52") (pin "2") (pinfunction "2_2") (pintype "passive"))
      (node (ref "R54") (pin "2") (pinfunction "2_2") (pintype "passive"))
      (node (ref "R56") (pin "2") (pinfunction "2_2") (pintype "passive"))
      (node (ref "R58") (pin "2") (pinfunction "2_2") (pintype "passive"))
      (node (ref "R6") (pin "2") (pinfunction "2_2") (pintype "passive"))
      (node (ref "R60") (pin "2") (pinfunction "2_2") (pintype "passive"))
      (node (ref "R62") (pin "2") (pinfunction "2_2") (pintype "passive"))
      (node (ref "R8") (pin "2") (pinfunction "2_2") (pintype "passive"))
      (node (ref "SW1") (pin "1") (pinfunction "1_1") (pintype "passive"))
      (node (ref "U1") (pin "23") (pinfunction "VSS_1_23") (pintype "power_in"))
      (node (ref "U1") (pin "35") (pinfunction "VSS_2_35") (pintype "power_in"))
      (node (ref "U1") (pin "47") (pinfunction "VSS_3_47") (pintype "power_in"))
      (node (ref "U1") (pin "8") (pinfunction "VSSA_8") (pintype "power_in"))
      (node (ref "Y1") (pin "2") (pinfunction "GND_2") (pintype "power_in"))
      (node (ref "Y1") (pin "4") (pinfunction "GND_4") (pintype "power_in"))
    )
    (net (code "41") (name "Net-(U1A-BOOT0)") (class "Default")
      (node (ref "R2") (pin "1") (pinfunction "1_1") (pintype "passive"))
      (node (ref "U1") (pin "44") (pinfunction "BOOT0_44") (pintype "passive"))
    )
    (net (code "42") (name "Net-(U1A-PD1-OSC_OUT)") (class "Default")
      (node (ref "R1") (pin "2") (pinfunction "2_2") (pintype "passive"))
      (node (ref "U1") (pin "6") (pinfunction "PD1-OSC_OUT_6") (pintype "passive"))
    )
    (net (code "43") (name "unconnected-(U1A-PC13-TAMPER-RTC-Pad2)") (class "Default")
      (node (ref "U1") (pin "2") (pinfunction "PC13-TAMPER-RTC_2") (pintype "passive"))
    )
    (net (code "44") (name "unconnected-(U1B-VBAT-Pad1)") (class "Default")
      (node (ref "U1") (pin "1") (pinfunction "VBAT_1") (pintype "power_in"))
    )
  )
)
